# main.net
KiCad netlist of a schematic drawn in EAGLE
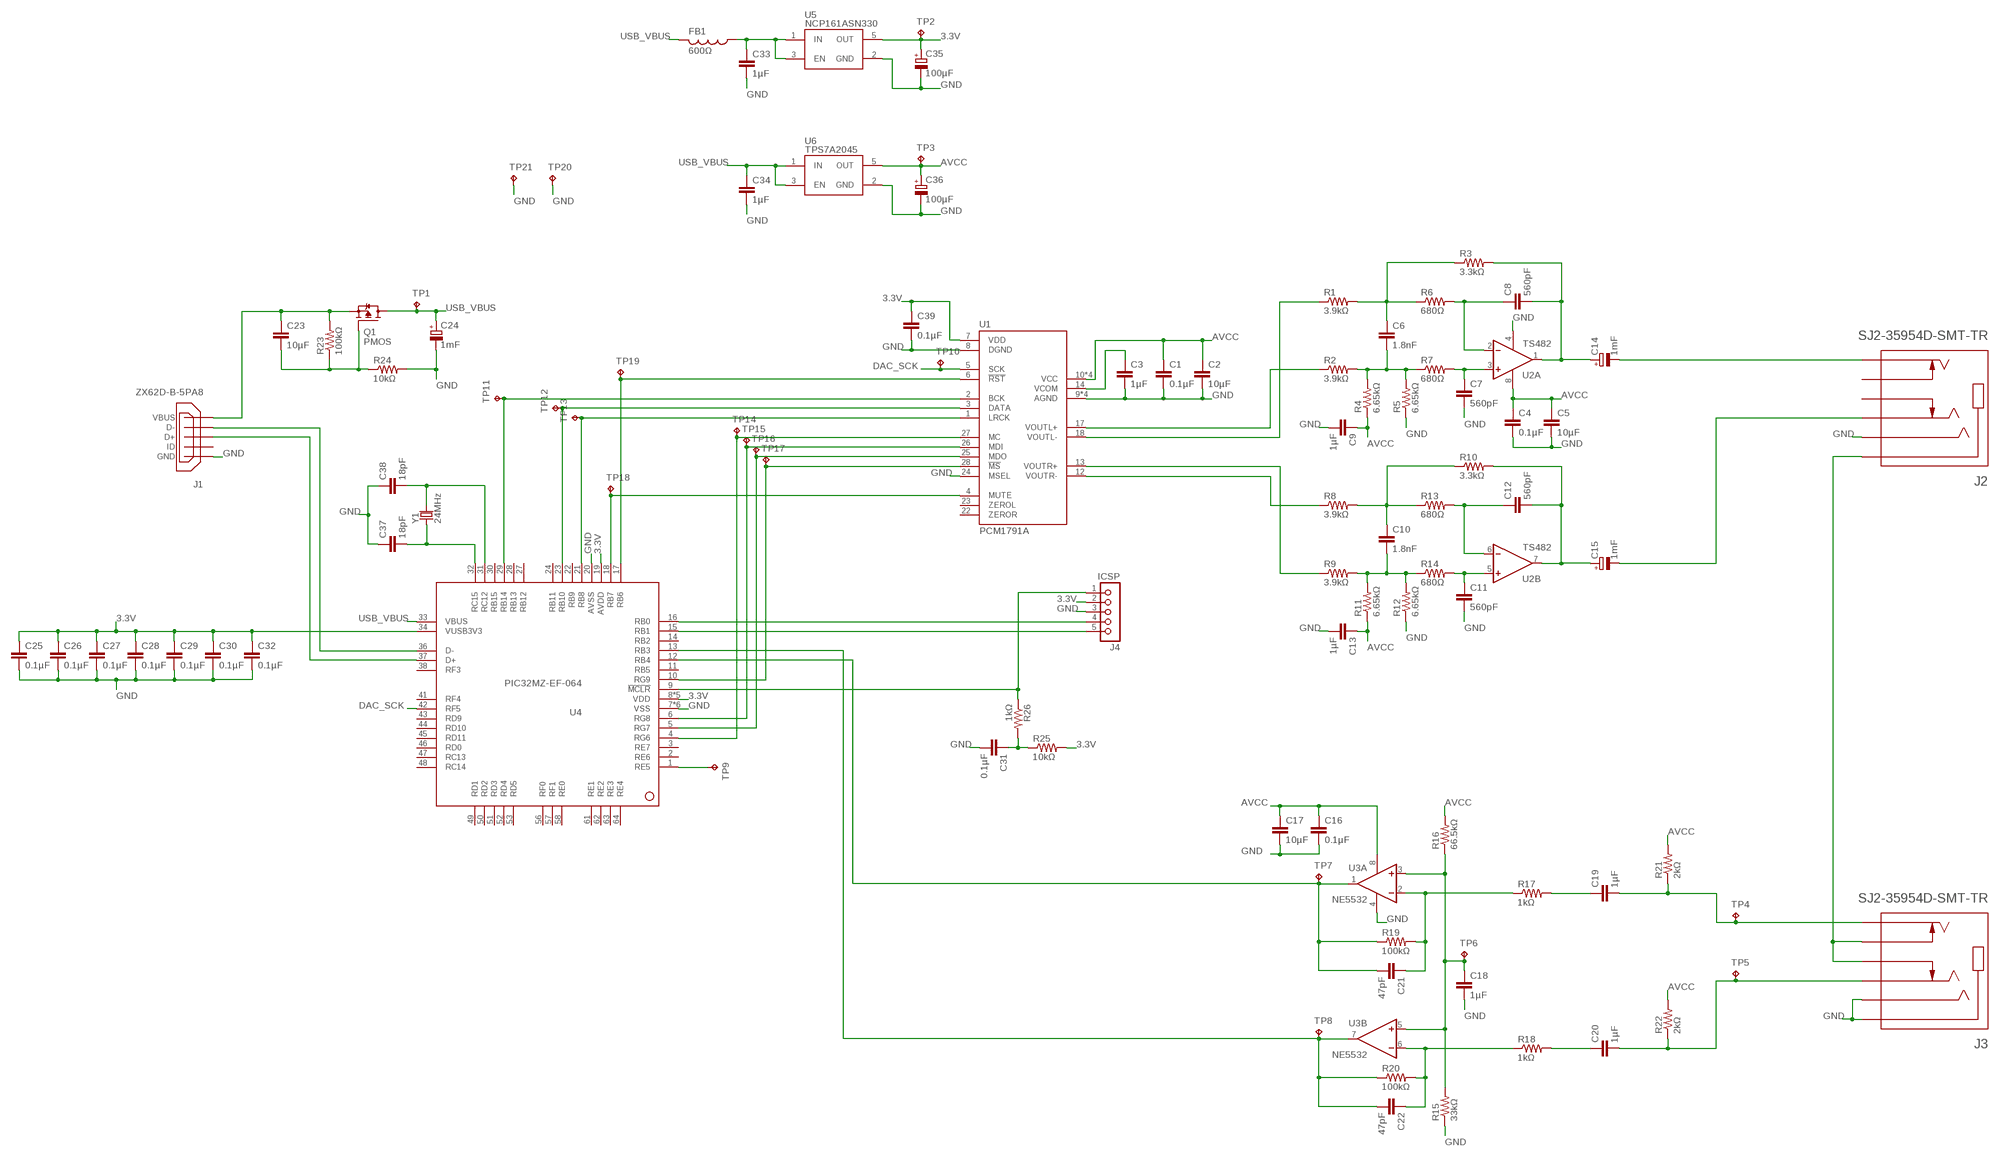
[diagram p0: schematic, sheet 1]

(export (version "E")
  (design (tool "Eeschema 10.0.6"))
  (components
    (comp (ref "C1")
      (value "0.1µF")
      (footprint "eagle-import:C0603")
      (libsource (lib "eagle-import") (part "C-EUC0603"))
    )
    (comp (ref "C2")
      (value "10µF")
      (footprint "eagle-import:C0805")
      (libsource (lib "eagle-import") (part "C-EUC0805"))
    )
    (comp (ref "C3")
      (value "1µF")
      (footprint "eagle-import:C0805")
      (libsource (lib "eagle-import") (part "C-EUC0805"))
    )
    (comp (ref "C4")
      (value "0.1µF")
      (footprint "eagle-import:C0603")
      (libsource (lib "eagle-import") (part "C-EUC0603"))
    )
    (comp (ref "C5")
      (value "10µF")
      (footprint "eagle-import:C0805")
      (libsource (lib "eagle-import") (part "C-EUC0805"))
    )
    (comp (ref "C6")
      (value "1.8nF")
      (footprint "eagle-import:C0603")
      (libsource (lib "eagle-import") (part "C-EUC0603"))
    )
    (comp (ref "C7")
      (value "560pF")
      (footprint "eagle-import:C0603")
      (libsource (lib "eagle-import") (part "C-EUC0603"))
    )
    (comp (ref "C8")
      (value "560pF")
      (footprint "eagle-import:C0603")
      (libsource (lib "eagle-import") (part "C-EUC0603"))
    )
    (comp (ref "C9")
      (value "1µF")
      (footprint "eagle-import:C0805")
      (libsource (lib "eagle-import") (part "C-EUC0805"))
    )
    (comp (ref "C10")
      (value "1.8nF")
      (footprint "eagle-import:C0603")
      (libsource (lib "eagle-import") (part "C-EUC0603"))
    )
    (comp (ref "C11")
      (value "560pF")
      (footprint "eagle-import:C0603")
      (libsource (lib "eagle-import") (part "C-EUC0603"))
    )
    (comp (ref "C12")
      (value "560pF")
      (footprint "eagle-import:C0603")
      (libsource (lib "eagle-import") (part "C-EUC0603"))
    )
    (comp (ref "C13")
      (value "1µF")
      (footprint "eagle-import:C0805")
      (libsource (lib "eagle-import") (part "C-EUC0805"))
    )
    (comp (ref "C14")
      (value "1mF")
      (footprint "eagle-import:E3,5-8-16-HORZ")
      (libsource (lib "eagle-import") (part "CAP-E3,5-8-16-HORZ"))
    )
    (comp (ref "C15")
      (value "1mF")
      (footprint "eagle-import:E3,5-8-16-HORZ")
      (libsource (lib "eagle-import") (part "CAP-E3,5-8-16-HORZ"))
    )
    (comp (ref "C16")
      (value "0.1µF")
      (footprint "eagle-import:C0603")
      (libsource (lib "eagle-import") (part "C-EUC0603"))
    )
    (comp (ref "C17")
      (value "10µF")
      (footprint "eagle-import:C0805")
      (libsource (lib "eagle-import") (part "C-EUC0805"))
    )
    (comp (ref "C18")
      (value "1µF")
      (footprint "eagle-import:C0805")
      (libsource (lib "eagle-import") (part "C-EUC0805"))
    )
    (comp (ref "C19")
      (value "1µF")
      (footprint "eagle-import:C050-050X075")
      (libsource (lib "eagle-import") (part "C-EU050-050X075"))
    )
    (comp (ref "C20")
      (value "1µF")
      (footprint "eagle-import:C050-050X075")
      (libsource (lib "eagle-import") (part "C-EU050-050X075"))
    )
    (comp (ref "C21")
      (value "47pF")
      (footprint "eagle-import:C050-045X075")
      (libsource (lib "eagle-import") (part "C-EU050-045X075"))
    )
    (comp (ref "C22")
      (value "47pF")
      (footprint "eagle-import:C050-045X075")
      (libsource (lib "eagle-import") (part "C-EU050-045X075"))
    )
    (comp (ref "C23")
      (value "10µF")
      (footprint "eagle-import:C0805")
      (libsource (lib "eagle-import") (part "C-EUC0805"))
    )
    (comp (ref "C24")
      (value "1mF")
      (footprint "eagle-import:E3,5-8-16-HORZ")
      (libsource (lib "eagle-import") (part "CAP-E3,5-8-16-HORZ"))
    )
    (comp (ref "C25")
      (value "0.1µF")
      (footprint "eagle-import:C0603")
      (libsource (lib "eagle-import") (part "C-EUC0603"))
    )
    (comp (ref "C26")
      (value "0.1µF")
      (footprint "eagle-import:C0603")
      (libsource (lib "eagle-import") (part "C-EUC0603"))
    )
    (comp (ref "C27")
      (value "0.1µF")
      (footprint "eagle-import:C0603")
      (libsource (lib "eagle-import") (part "C-EUC0603"))
    )
    (comp (ref "C28")
      (value "0.1µF")
      (footprint "eagle-import:C0603")
      (libsource (lib "eagle-import") (part "C-EUC0603"))
    )
    (comp (ref "C29")
      (value "0.1µF")
      (footprint "eagle-import:C0603")
      (libsource (lib "eagle-import") (part "C-EUC0603"))
    )
    (comp (ref "C30")
      (value "0.1µF")
      (footprint "eagle-import:C0603")
      (libsource (lib "eagle-import") (part "C-EUC0603"))
    )
    (comp (ref "C31")
      (value "0.1µF")
      (footprint "eagle-import:C0603")
      (libsource (lib "eagle-import") (part "C-EUC0603"))
    )
    (comp (ref "C32")
      (value "0.1µF")
      (footprint "eagle-import:C0603")
      (libsource (lib "eagle-import") (part "C-EUC0603"))
    )
    (comp (ref "C33")
      (value "1µF")
      (footprint "eagle-import:C0805")
      (libsource (lib "eagle-import") (part "C-EUC0805"))
    )
    (comp (ref "C34")
      (value "1µF")
      (footprint "eagle-import:C0805")
      (libsource (lib "eagle-import") (part "C-EUC0805"))
    )
    (comp (ref "C35")
      (value "100µF")
      (footprint "eagle-import:PANASONIC_D")
      (libsource (lib "eagle-import") (part "CPOL-EUD"))
    )
    (comp (ref "C36")
      (value "100µF")
      (footprint "eagle-import:PANASONIC_D")
      (libsource (lib "eagle-import") (part "CPOL-EUD"))
    )
    (comp (ref "C37")
      (value "18pF")
      (footprint "eagle-import:C0603")
      (libsource (lib "eagle-import") (part "C-EUC0603"))
    )
    (comp (ref "C38")
      (value "18pF")
      (footprint "eagle-import:C0603")
      (libsource (lib "eagle-import") (part "C-EUC0603"))
    )
    (comp (ref "C39")
      (value "0.1µF")
      (footprint "eagle-import:C0603")
      (libsource (lib "eagle-import") (part "C-EUC0603"))
    )
    (comp (ref "FB1")
      (value "600Ω")
      (footprint "eagle-import:C0603")
      (libsource (lib "eagle-import") (part "0603-FERRITE"))
    )
    (comp (ref "J1")
      (value "ZX62D-B-5PA8")
      (footprint "eagle-import:ZX62D-B-5PA8")
      (libsource (lib "eagle-import") (part "ZX62D-B-5PA8"))
    )
    (comp (ref "J2")
      (value "SJ2-35954D-SMT-TR")
      (footprint "eagle-import:CUI_SJ2-35954D-SMT-TR")
      (fields (field (name "MANUFACTURER") "CUI"))
      (libsource (lib "eagle-import") (part "SJ2-35954D-SMT-TR"))
    )
    (comp (ref "J3")
      (value "SJ2-35954D-SMT-TR")
      (footprint "eagle-import:CUI_SJ2-35954D-SMT-TR")
      (fields (field (name "MANUFACTURER") "CUI"))
      (libsource (lib "eagle-import") (part "SJ2-35954D-SMT-TR"))
    )
    (comp (ref "J4")
      (value "ICSP")
      (footprint "eagle-import:5PIN-1.27")
      (libsource (lib "eagle-import") (part "5PIN-1.27"))
    )
    (comp (ref "Q1")
      (value "PMOS")
      (footprint "eagle-import:SOT23")
      (libsource (lib "eagle-import") (part "SOT23-P-MOSFET"))
    )
    (comp (ref "R1")
      (value "3.9kΩ")
      (footprint "eagle-import:R0603")
      (libsource (lib "eagle-import") (part "R-US_R0603"))
    )
    (comp (ref "R2")
      (value "3.9kΩ")
      (footprint "eagle-import:R0603")
      (libsource (lib "eagle-import") (part "R-US_R0603"))
    )
    (comp (ref "R3")
      (value "3.3kΩ")
      (footprint "eagle-import:R0603")
      (libsource (lib "eagle-import") (part "R-US_R0603"))
    )
    (comp (ref "R4")
      (value "6.65kΩ")
      (footprint "eagle-import:R0603")
      (libsource (lib "eagle-import") (part "R-US_R0603"))
    )
    (comp (ref "R5")
      (value "6.65kΩ")
      (footprint "eagle-import:R0603")
      (libsource (lib "eagle-import") (part "R-US_R0603"))
    )
    (comp (ref "R6")
      (value "680Ω")
      (footprint "eagle-import:R0603")
      (libsource (lib "eagle-import") (part "R-US_R0603"))
    )
    (comp (ref "R7")
      (value "680Ω")
      (footprint "eagle-import:R0603")
      (libsource (lib "eagle-import") (part "R-US_R0603"))
    )
    (comp (ref "R8")
      (value "3.9kΩ")
      (footprint "eagle-import:R0603")
      (libsource (lib "eagle-import") (part "R-US_R0603"))
    )
    (comp (ref "R9")
      (value "3.9kΩ")
      (footprint "eagle-import:R0603")
      (libsource (lib "eagle-import") (part "R-US_R0603"))
    )
    (comp (ref "R10")
      (value "3.3kΩ")
      (footprint "eagle-import:R0603")
      (libsource (lib "eagle-import") (part "R-US_R0603"))
    )
    (comp (ref "R11")
      (value "6.65kΩ")
      (footprint "eagle-import:R0603")
      (libsource (lib "eagle-import") (part "R-US_R0603"))
    )
    (comp (ref "R12")
      (value "6.65kΩ")
      (footprint "eagle-import:R0603")
      (libsource (lib "eagle-import") (part "R-US_R0603"))
    )
    (comp (ref "R13")
      (value "680Ω")
      (footprint "eagle-import:R0603")
      (libsource (lib "eagle-import") (part "R-US_R0603"))
    )
    (comp (ref "R14")
      (value "680Ω")
      (footprint "eagle-import:R0603")
      (libsource (lib "eagle-import") (part "R-US_R0603"))
    )
    (comp (ref "R15")
      (value "33kΩ")
      (footprint "eagle-import:R0603")
      (libsource (lib "eagle-import") (part "R-US_R0603"))
    )
    (comp (ref "R16")
      (value "66.5kΩ")
      (footprint "eagle-import:R0603")
      (libsource (lib "eagle-import") (part "R-US_R0603"))
    )
    (comp (ref "R17")
      (value "1kΩ")
      (footprint "eagle-import:R0603")
      (libsource (lib "eagle-import") (part "R-US_R0603"))
    )
    (comp (ref "R18")
      (value "1kΩ")
      (footprint "eagle-import:R0603")
      (libsource (lib "eagle-import") (part "R-US_R0603"))
    )
    (comp (ref "R19")
      (value "100kΩ")
      (footprint "eagle-import:R0603")
      (libsource (lib "eagle-import") (part "R-US_R0603"))
    )
    (comp (ref "R20")
      (value "100kΩ")
      (footprint "eagle-import:R0603")
      (libsource (lib "eagle-import") (part "R-US_R0603"))
    )
    (comp (ref "R21")
      (value "2kΩ")
      (footprint "eagle-import:R0603")
      (libsource (lib "eagle-import") (part "R-US_R0603"))
    )
    (comp (ref "R22")
      (value "2kΩ")
      (footprint "eagle-import:R0603")
      (libsource (lib "eagle-import") (part "R-US_R0603"))
    )
    (comp (ref "R23")
      (value "100kΩ")
      (footprint "eagle-import:R0603")
      (libsource (lib "eagle-import") (part "R-US_R0603"))
    )
    (comp (ref "R24")
      (value "10kΩ")
      (footprint "eagle-import:R0603")
      (libsource (lib "eagle-import") (part "R-US_R0603"))
    )
    (comp (ref "R25")
      (value "10kΩ")
      (footprint "eagle-import:R0603")
      (libsource (lib "eagle-import") (part "R-US_R0603"))
    )
    (comp (ref "R26")
      (value "1kΩ")
      (footprint "eagle-import:R0603")
      (libsource (lib "eagle-import") (part "R-US_R0603"))
    )
    (comp (ref "TP1")
      (value "RCU-0(J)")
      (footprint "eagle-import:TP_0603_JOINED")
      (libsource (lib "eagle-import") (part "RCU-0(J)"))
    )
    (comp (ref "TP2")
      (value "RCU-0(J)")
      (footprint "eagle-import:TP_0603_JOINED")
      (libsource (lib "eagle-import") (part "RCU-0(J)"))
    )
    (comp (ref "TP3")
      (value "RCU-0(J)")
      (footprint "eagle-import:TP_0603_JOINED")
      (libsource (lib "eagle-import") (part "RCU-0(J)"))
    )
    (comp (ref "TP4")
      (value "RCU-0(J)")
      (footprint "eagle-import:TP_0603_JOINED")
      (libsource (lib "eagle-import") (part "RCU-0(J)"))
    )
    (comp (ref "TP5")
      (value "RCU-0(J)")
      (footprint "eagle-import:TP_0603_JOINED")
      (libsource (lib "eagle-import") (part "RCU-0(J)"))
    )
    (comp (ref "TP6")
      (value "RCU-0(J)")
      (footprint "eagle-import:TP_0603_JOINED")
      (libsource (lib "eagle-import") (part "RCU-0(J)"))
    )
    (comp (ref "TP7")
      (value "RCU-0(J)")
      (footprint "eagle-import:TP_0603_JOINED")
      (libsource (lib "eagle-import") (part "RCU-0(J)"))
    )
    (comp (ref "TP8")
      (value "RCU-0(J)")
      (footprint "eagle-import:TP_0603_JOINED")
      (libsource (lib "eagle-import") (part "RCU-0(J)"))
    )
    (comp (ref "TP9")
      (value "RCU-0(J)")
      (footprint "eagle-import:TP_0603_JOINED")
      (libsource (lib "eagle-import") (part "RCU-0(J)"))
    )
    (comp (ref "TP10")
      (value "RCU-0(J)")
      (footprint "eagle-import:TP_0603_JOINED")
      (libsource (lib "eagle-import") (part "RCU-0(J)"))
    )
    (comp (ref "TP11")
      (value "RCU-0(J)")
      (footprint "eagle-import:TP_0603_JOINED")
      (libsource (lib "eagle-import") (part "RCU-0(J)"))
    )
    (comp (ref "TP12")
      (value "RCU-0(J)")
      (footprint "eagle-import:TP_0603_JOINED")
      (libsource (lib "eagle-import") (part "RCU-0(J)"))
    )
    (comp (ref "TP13")
      (value "RCU-0(J)")
      (footprint "eagle-import:TP_0603_JOINED")
      (libsource (lib "eagle-import") (part "RCU-0(J)"))
    )
    (comp (ref "TP14")
      (value "RCU-0(J)")
      (footprint "eagle-import:TP_0603_JOINED")
      (libsource (lib "eagle-import") (part "RCU-0(J)"))
    )
    (comp (ref "TP15")
      (value "RCU-0(J)")
      (footprint "eagle-import:TP_0603_JOINED")
      (libsource (lib "eagle-import") (part "RCU-0(J)"))
    )
    (comp (ref "TP16")
      (value "RCU-0(J)")
      (footprint "eagle-import:TP_0603_JOINED")
      (libsource (lib "eagle-import") (part "RCU-0(J)"))
    )
    (comp (ref "TP17")
      (value "RCU-0(J)")
      (footprint "eagle-import:TP_0603_JOINED")
      (libsource (lib "eagle-import") (part "RCU-0(J)"))
    )
    (comp (ref "TP18")
      (value "RCU-0(J)")
      (footprint "eagle-import:TP_0603_JOINED")
      (libsource (lib "eagle-import") (part "RCU-0(J)"))
    )
    (comp (ref "TP19")
      (value "RCU-0(J)")
      (footprint "eagle-import:TP_0603_JOINED")
      (libsource (lib "eagle-import") (part "RCU-0(J)"))
    )
    (comp (ref "TP20")
      (value "RCU-0(J)")
      (footprint "eagle-import:TP_0603_JOINED")
      (libsource (lib "eagle-import") (part "RCU-0(J)"))
    )
    (comp (ref "TP21")
      (value "RCU-0(J)")
      (footprint "eagle-import:TP_0603_JOINED")
      (libsource (lib "eagle-import") (part "RCU-0(J)"))
    )
    (comp (ref "U1")
      (value "PCM1791A")
      (footprint "eagle-import:SSOP28")
      (libsource (lib "eagle-import") (part "PCM1791A"))
    )
    (comp (ref "U2")
      (value "TS482")
      (footprint "eagle-import:MSOP8")
      (libsource (lib "eagle-import") (part "TS482"))
    )
    (comp (ref "U3")
      (value "NE5532")
      (footprint "eagle-import:SOIC8")
      (libsource (lib "eagle-import") (part "NE5532"))
    )
    (comp (ref "U4")
      (value "PIC32MZ-EF-064")
      (footprint "eagle-import:TQFP64-10X10X1MM")
      (libsource (lib "eagle-import") (part "PIC32MZ-EF-064"))
    )
    (comp (ref "U5")
      (value "NCP161ASN330")
      (footprint "eagle-import:SOT23-5L")
      (libsource (lib "eagle-import") (part "SOT23-5-LDO"))
    )
    (comp (ref "U6")
      (value "TPS7A2045")
      (footprint "eagle-import:SOT23-5L")
      (libsource (lib "eagle-import") (part "SOT23-5-LDO"))
    )
    (comp (ref "Y1")
      (value "24MHz")
      (footprint "eagle-import:HC49_4HSMX")
      (libsource (lib "eagle-import") (part "HC49/4HSMX-CRYSTAL"))
    )
  )
  (nets
    (net (code "1") (name "/3.3V") (class "Default")
      (node (ref "C25") (pin "1") (pinfunction "1_1") (pintype "passive"))
      (node (ref "C26") (pin "1") (pinfunction "1_1") (pintype "passive"))
      (node (ref "C27") (pin "1") (pinfunction "1_1") (pintype "passive"))
      (node (ref "C28") (pin "1") (pinfunction "1_1") (pintype "passive"))
      (node (ref "C29") (pin "1") (pinfunction "1_1") (pintype "passive"))
      (node (ref "C30") (pin "1") (pinfunction "1_1") (pintype "passive"))
      (node (ref "C32") (pin "1") (pinfunction "1_1") (pintype "passive"))
      (node (ref "C35") (pin "+") (pinfunction "+_+") (pintype "passive"))
      (node (ref "C39") (pin "1") (pinfunction "1_1") (pintype "passive"))
      (node (ref "J4") (pin "2") (pinfunction "2_2") (pintype "passive"))
      (node (ref "R25") (pin "2") (pinfunction "2_2") (pintype "passive"))
      (node (ref "TP2") (pin "1") (pinfunction "TP_1") (pintype "input"))
      (node (ref "U1") (pin "7") (pinfunction "VDD_7") (pintype "bidirectional"))
      (node (ref "U4") (pin "19") (pinfunction "AVDD_19") (pintype "bidirectional"))
      (node (ref "U4") (pin "26") (pinfunction "VDD_26") (pintype "bidirectional"))
      (node (ref "U4") (pin "34") (pinfunction "VUSB3V3_34") (pintype "bidirectional"))
      (node (ref "U4") (pin "39") (pinfunction "VDD_39") (pintype "bidirectional"))
      (node (ref "U4") (pin "54") (pinfunction "VDD_54") (pintype "bidirectional"))
      (node (ref "U4") (pin "60") (pinfunction "VDD_60") (pintype "bidirectional"))
      (node (ref "U4") (pin "8") (pinfunction "VDD_8") (pintype "bidirectional"))
      (node (ref "U5") (pin "5") (pinfunction "OUT_5") (pintype "bidirectional"))
    )
    (net (code "2") (name "/AVCC") (class "Default")
      (node (ref "C1") (pin "1") (pinfunction "1_1") (pintype "passive"))
      (node (ref "C13") (pin "1") (pinfunction "1_1") (pintype "passive"))
      (node (ref "C16") (pin "1") (pinfunction "1_1") (pintype "passive"))
      (node (ref "C17") (pin "1") (pinfunction "1_1") (pintype "passive"))
      (node (ref "C2") (pin "1") (pinfunction "1_1") (pintype "passive"))
      (node (ref "C36") (pin "+") (pinfunction "+_+") (pintype "passive"))
      (node (ref "C4") (pin "1") (pinfunction "1_1") (pintype "passive"))
      (node (ref "C5") (pin "1") (pinfunction "1_1") (pintype "passive"))
      (node (ref "C9") (pin "1") (pinfunction "1_1") (pintype "passive"))
      (node (ref "R11") (pin "1") (pinfunction "1_1") (pintype "passive"))
      (node (ref "R16") (pin "2") (pinfunction "2_2") (pintype "passive"))
      (node (ref "R21") (pin "2") (pinfunction "2_2") (pintype "passive"))
      (node (ref "R22") (pin "2") (pinfunction "2_2") (pintype "passive"))
      (node (ref "R4") (pin "1") (pinfunction "1_1") (pintype "passive"))
      (node (ref "TP3") (pin "1") (pinfunction "TP_1") (pintype "input"))
      (node (ref "U1") (pin "10") (pinfunction "VCC_10") (pintype "bidirectional"))
      (node (ref "U1") (pin "15") (pinfunction "VCC_15") (pintype "bidirectional"))
      (node (ref "U1") (pin "20") (pinfunction "VCC_20") (pintype "bidirectional"))
      (node (ref "U1") (pin "21") (pinfunction "VCC_21") (pintype "bidirectional"))
      (node (ref "U2") (pin "8") (pinfunction "V+_8") (pintype "power_in"))
      (node (ref "U3") (pin "8") (pinfunction "V+_8") (pintype "power_in"))
      (node (ref "U6") (pin "5") (pinfunction "OUT_5") (pintype "bidirectional"))
    )
    (net (code "3") (name "/DAC_SCK") (class "Default")
      (node (ref "TP10") (pin "1") (pinfunction "TP_1") (pintype "input"))
      (node (ref "U1") (pin "5") (pinfunction "SCK_5") (pintype "bidirectional"))
      (node (ref "U4") (pin "42") (pinfunction "RF5_42") (pintype "bidirectional"))
    )
    (net (code "4") (name "/GND") (class "Default")
      (node (ref "C1") (pin "2") (pinfunction "2_2") (pintype "passive"))
      (node (ref "C11") (pin "2") (pinfunction "2_2") (pintype "passive"))
      (node (ref "C13") (pin "2") (pinfunction "2_2") (pintype "passive"))
      (node (ref "C16") (pin "2") (pinfunction "2_2") (pintype "passive"))
      (node (ref "C17") (pin "2") (pinfunction "2_2") (pintype "passive"))
      (node (ref "C18") (pin "2") (pinfunction "2_2") (pintype "passive"))
      (node (ref "C2") (pin "2") (pinfunction "2_2") (pintype "passive"))
      (node (ref "C24") (pin "-") (pinfunction "-_-") (pintype "passive"))
      (node (ref "C25") (pin "2") (pinfunction "2_2") (pintype "passive"))
      (node (ref "C26") (pin "2") (pinfunction "2_2") (pintype "passive"))
      (node (ref "C27") (pin "2") (pinfunction "2_2") (pintype "passive"))
      (node (ref "C28") (pin "2") (pinfunction "2_2") (pintype "passive"))
      (node (ref "C29") (pin "2") (pinfunction "2_2") (pintype "passive"))
      (node (ref "C3") (pin "2") (pinfunction "2_2") (pintype "passive"))
      (node (ref "C30") (pin "2") (pinfunction "2_2") (pintype "passive"))
      (node (ref "C31") (pin "2") (pinfunction "2_2") (pintype "passive"))
      (node (ref "C32") (pin "2") (pinfunction "2_2") (pintype "passive"))
      (node (ref "C33") (pin "2") (pinfunction "2_2") (pintype "passive"))
      (node (ref "C34") (pin "2") (pinfunction "2_2") (pintype "passive"))
      (node (ref "C35") (pin "-") (pinfunction "-_-") (pintype "passive"))
      (node (ref "C36") (pin "-") (pinfunction "-_-") (pintype "passive"))
      (node (ref "C37") (pin "1") (pinfunction "1_1") (pintype "passive"))
      (node (ref "C38") (pin "1") (pinfunction "1_1") (pintype "passive"))
      (node (ref "C39") (pin "2") (pinfunction "2_2") (pintype "passive"))
      (node (ref "C4") (pin "2") (pinfunction "2_2") (pintype "passive"))
      (node (ref "C5") (pin "2") (pinfunction "2_2") (pintype "passive"))
      (node (ref "C7") (pin "2") (pinfunction "2_2") (pintype "passive"))
      (node (ref "C9") (pin "2") (pinfunction "2_2") (pintype "passive"))
      (node (ref "J1") (pin "5") (pinfunction "GND_5") (pintype "passive"))
      (node (ref "J1") (pin "S1") (pinfunction "GND_S1") (pintype "passive"))
      (node (ref "J1") (pin "S2") (pinfunction "GND_S2") (pintype "passive"))
      (node (ref "J1") (pin "S3") (pinfunction "GND_S3") (pintype "passive"))
      (node (ref "J1") (pin "S4") (pinfunction "GND_S4") (pintype "passive"))
      (node (ref "J2") (pin "4") (pinfunction "RING2_4") (pintype "passive"))
      (node (ref "J3") (pin "1") (pinfunction "SLEEVE_1") (pintype "passive"))
      (node (ref "J3") (pin "4") (pinfunction "RING2_4") (pintype "passive"))
      (node (ref "J4") (pin "3") (pinfunction "3_3") (pintype "passive"))
      (node (ref "R12") (pin "1") (pinfunction "1_1") (pintype "passive"))
      (node (ref "R15") (pin "1") (pinfunction "1_1") (pintype "passive"))
      (node (ref "R24") (pin "2") (pinfunction "2_2") (pintype "passive"))
      (node (ref "R5") (pin "1") (pinfunction "1_1") (pintype "passive"))
      (node (ref "TP20") (pin "1") (pinfunction "TP_1") (pintype "input"))
      (node (ref "TP21") (pin "1") (pinfunction "TP_1") (pintype "input"))
      (node (ref "U1") (pin "11") (pinfunction "AGND_11") (pintype "bidirectional"))
      (node (ref "U1") (pin "16") (pinfunction "AGND_16") (pintype "bidirectional"))
      (node (ref "U1") (pin "19") (pinfunction "AGND_19") (pintype "bidirectional"))
      (node (ref "U1") (pin "24") (pinfunction "MSEL_24") (pintype "bidirectional"))
      (node (ref "U1") (pin "8") (pinfunction "DGND_8") (pintype "bidirectional"))
      (node (ref "U1") (pin "9") (pinfunction "AGND_9") (pintype "bidirectional"))
      (node (ref "U2") (pin "4") (pinfunction "V-_4") (pintype "power_in"))
      (node (ref "U3") (pin "4") (pinfunction "V-_4") (pintype "power_in"))
      (node (ref "U4") (pin "20") (pinfunction "AVSS_20") (pintype "bidirectional"))
      (node (ref "U4") (pin "25") (pinfunction "VSS_25") (pintype "bidirectional"))
      (node (ref "U4") (pin "35") (pinfunction "VSS_35") (pintype "bidirectional"))
      (node (ref "U4") (pin "40") (pinfunction "VSS_40") (pintype "bidirectional"))
      (node (ref "U4") (pin "55") (pinfunction "VSS_55") (pintype "bidirectional"))
      (node (ref "U4") (pin "59") (pinfunction "VSS_59") (pintype "bidirectional"))
      (node (ref "U4") (pin "7") (pinfunction "VSS_7") (pintype "bidirectional"))
      (node (ref "U5") (pin "2") (pinfunction "GND_2") (pintype "bidirectional"))
      (node (ref "U6") (pin "2") (pinfunction "GND_2") (pintype "bidirectional"))
    )
    (net (code "5") (name "/USB_VBUS") (class "Default")
      (node (ref "C24") (pin "+") (pinfunction "+_+") (pintype "passive"))
      (node (ref "C34") (pin "1") (pinfunction "1_1") (pintype "passive"))
      (node (ref "FB1") (pin "2") (pinfunction "2_2") (pintype "passive"))
      (node (ref "Q1") (pin "3") (pinfunction "D_3") (pintype "passive"))
      (node (ref "TP1") (pin "1") (pinfunction "TP_1") (pintype "input"))
      (node (ref "U4") (pin "33") (pinfunction "VBUS_33") (pintype "bidirectional"))
      (node (ref "U6") (pin "1") (pinfunction "IN_1") (pintype "bidirectional"))
      (node (ref "U6") (pin "3") (pinfunction "EN_3") (pintype "bidirectional"))
    )
    (net (code "6") (name "Net-(C6-Pad1)") (class "Default")
      (node (ref "C6") (pin "1") (pinfunction "1_1") (pintype "passive"))
      (node (ref "R1") (pin "2") (pinfunction "2_2") (pintype "passive"))
      (node (ref "R3") (pin "1") (pinfunction "1_1") (pintype "passive"))
      (node (ref "R6") (pin "1") (pinfunction "1_1") (pintype "passive"))
    )
    (net (code "7") (name "Net-(C6-Pad2)") (class "Default")
      (node (ref "C6") (pin "2") (pinfunction "2_2") (pintype "passive"))
      (node (ref "R2") (pin "2") (pinfunction "2_2") (pintype "passive"))
      (node (ref "R4") (pin "2") (pinfunction "2_2") (pintype "passive"))
      (node (ref "R5") (pin "2") (pinfunction "2_2") (pintype "passive"))
      (node (ref "R7") (pin "1") (pinfunction "1_1") (pintype "passive"))
    )
    (net (code "8") (name "Net-(C10-Pad1)") (class "Default")
      (node (ref "C10") (pin "1") (pinfunction "1_1") (pintype "passive"))
      (node (ref "R10") (pin "1") (pinfunction "1_1") (pintype "passive"))
      (node (ref "R13") (pin "1") (pinfunction "1_1") (pintype "passive"))
      (node (ref "R8") (pin "2") (pinfunction "2_2") (pintype "passive"))
    )
    (net (code "9") (name "Net-(C10-Pad2)") (class "Default")
      (node (ref "C10") (pin "2") (pinfunction "2_2") (pintype "passive"))
      (node (ref "R11") (pin "2") (pinfunction "2_2") (pintype "passive"))
      (node (ref "R12") (pin "2") (pinfunction "2_2") (pintype "passive"))
      (node (ref "R14") (pin "1") (pinfunction "1_1") (pintype "passive"))
      (node (ref "R9") (pin "2") (pinfunction "2_2") (pintype "passive"))
    )
    (net (code "10") (name "Net-(C19-Pad1)") (class "Default")
      (node (ref "C19") (pin "1") (pinfunction "1_1") (pintype "passive"))
      (node (ref "R17") (pin "2") (pinfunction "2_2") (pintype "passive"))
    )
    (net (code "11") (name "Net-(C20-Pad1)") (class "Default")
      (node (ref "C20") (pin "1") (pinfunction "1_1") (pintype "passive"))
      (node (ref "R18") (pin "2") (pinfunction "2_2") (pintype "passive"))
    )
    (net (code "12") (name "Net-(C31-Pad1)") (class "Default")
      (node (ref "C31") (pin "1") (pinfunction "1_1") (pintype "passive"))
      (node (ref "R25") (pin "1") (pinfunction "1_1") (pintype "passive"))
      (node (ref "R26") (pin "2") (pinfunction "2_2") (pintype "passive"))
    )
    (net (code "13") (name "Net-(J1-D+)") (class "Default")
      (node (ref "J1") (pin "3") (pinfunction "D+_3") (pintype "passive"))
      (node (ref "U4") (pin "37") (pinfunction "D+_37") (pintype "bidirectional"))
    )
    (net (code "14") (name "Net-(J1-D-)") (class "Default")
      (node (ref "J1") (pin "2") (pinfunction "D-_2") (pintype "passive"))
      (node (ref "U4") (pin "36") (pinfunction "D-_36") (pintype "bidirectional"))
    )
    (net (code "15") (name "Net-(J1-VBUS)") (class "Default")
      (node (ref "C23") (pin "1") (pinfunction "1_1") (pintype "passive"))
      (node (ref "J1") (pin "1") (pinfunction "VBUS_1") (pintype "passive"))
      (node (ref "Q1") (pin "2") (pinfunction "S_2") (pintype "passive"))
      (node (ref "R23") (pin "2") (pinfunction "2_2") (pintype "passive"))
    )
    (net (code "16") (name "Net-(J2-RING1)") (class "Default")
      (node (ref "C15") (pin "-") (pinfunction "-_-") (pintype "passive"))
      (node (ref "J2") (pin "3") (pinfunction "RING1_3") (pintype "passive"))
    )
    (net (code "17") (name "Net-(J2-SLEEVE)") (class "Default")
      (node (ref "J2") (pin "1") (pinfunction "SLEEVE_1") (pintype "passive"))
      (node (ref "J3") (pin "10") (pinfunction "TIP_SWITCH_10") (pintype "passive"))
      (node (ref "J3") (pin "11") (pinfunction "RING1_SWITCH_11") (pintype "passive"))
    )
    (net (code "18") (name "Net-(J2-TIP)") (class "Default")
      (node (ref "C14") (pin "-") (pinfunction "-_-") (pintype "passive"))
      (node (ref "J2") (pin "2") (pinfunction "TIP_2") (pintype "passive"))
    )
    (net (code "19") (name "Net-(J3-RING1)") (class "Default")
      (node (ref "C20") (pin "2") (pinfunction "2_2") (pintype "passive"))
      (node (ref "J3") (pin "3") (pinfunction "RING1_3") (pintype "passive"))
      (node (ref "R22") (pin "1") (pinfunction "1_1") (pintype "passive"))
      (node (ref "TP5") (pin "1") (pinfunction "TP_1") (pintype "input"))
    )
    (net (code "20") (name "Net-(J3-TIP)") (class "Default")
      (node (ref "C19") (pin "2") (pinfunction "2_2") (pintype "passive"))
      (node (ref "J3") (pin "2") (pinfunction "TIP_2") (pintype "passive"))
      (node (ref "R21") (pin "1") (pinfunction "1_1") (pintype "passive"))
      (node (ref "TP4") (pin "1") (pinfunction "TP_1") (pintype "input"))
    )
    (net (code "21") (name "Net-(Q1-G)") (class "Default")
      (node (ref "C23") (pin "2") (pinfunction "2_2") (pintype "passive"))
      (node (ref "Q1") (pin "1") (pinfunction "G_1") (pintype "passive"))
      (node (ref "R23") (pin "1") (pinfunction "1_1") (pintype "passive"))
      (node (ref "R24") (pin "1") (pinfunction "1_1") (pintype "passive"))
    )
    (net (code "22") (name "Net-(TP6-TP)") (class "Default")
      (node (ref "C18") (pin "1") (pinfunction "1_1") (pintype "passive"))
      (node (ref "R15") (pin "2") (pinfunction "2_2") (pintype "passive"))
      (node (ref "R16") (pin "1") (pinfunction "1_1") (pintype "passive"))
      (node (ref "TP6") (pin "1") (pinfunction "TP_1") (pintype "input"))
      (node (ref "U3") (pin "3") (pinfunction "+IN_3") (pintype "input"))
      (node (ref "U3") (pin "5") (pinfunction "+IN_5") (pintype "input"))
    )
    (net (code "23") (name "Net-(TP7-TP)") (class "Default")
      (node (ref "C21") (pin "2") (pinfunction "2_2") (pintype "passive"))
      (node (ref "R19") (pin "1") (pinfunction "1_1") (pintype "passive"))
      (node (ref "TP7") (pin "1") (pinfunction "TP_1") (pintype "input"))
      (node (ref "U3") (pin "1") (pinfunction "OUT_1") (pintype "output"))
      (node (ref "U4") (pin "12") (pinfunction "RB4_12") (pintype "bidirectional"))
    )
    (net (code "24") (name "Net-(TP8-TP)") (class "Default")
      (node (ref "C22") (pin "2") (pinfunction "2_2") (pintype "passive"))
      (node (ref "R20") (pin "1") (pinfunction "1_1") (pintype "passive"))
      (node (ref "TP8") (pin "1") (pinfunction "TP_1") (pintype "input"))
      (node (ref "U3") (pin "7") (pinfunction "OUT_7") (pintype "output"))
      (node (ref "U4") (pin "13") (pinfunction "RB3_13") (pintype "bidirectional"))
    )
    (net (code "25") (name "Net-(TP9-TP)") (class "Default")
      (node (ref "TP9") (pin "1") (pinfunction "TP_1") (pintype "input"))
      (node (ref "U4") (pin "1") (pinfunction "RE5_1") (pintype "bidirectional"))
    )
    (net (code "26") (name "Net-(TP11-TP)") (class "Default")
      (node (ref "TP11") (pin "1") (pinfunction "TP_1") (pintype "input"))
      (node (ref "U1") (pin "2") (pinfunction "BCK_2") (pintype "bidirectional"))
      (node (ref "U4") (pin "29") (pinfunction "RB14_29") (pintype "bidirectional"))
    )
    (net (code "27") (name "Net-(TP12-TP)") (class "Default")
      (node (ref "TP12") (pin "1") (pinfunction "TP_1") (pintype "input"))
      (node (ref "U1") (pin "3") (pinfunction "DATA_3") (pintype "bidirectional"))
      (node (ref "U4") (pin "23") (pinfunction "RB10_23") (pintype "bidirectional"))
    )
    (net (code "28") (name "Net-(TP13-TP)") (class "Default")
      (node (ref "TP13") (pin "1") (pinfunction "TP_1") (pintype "input"))
      (node (ref "U1") (pin "1") (pinfunction "LRCK_1") (pintype "bidirectional"))
      (node (ref "U4") (pin "21") (pinfunction "RB8_21") (pintype "bidirectional"))
    )
    (net (code "29") (name "Net-(TP14-TP)") (class "Default")
      (node (ref "TP14") (pin "1") (pinfunction "TP_1") (pintype "input"))
      (node (ref "U1") (pin "27") (pinfunction "MC_27") (pintype "bidirectional"))
      (node (ref "U4") (pin "4") (pinfunction "RG6_4") (pintype "bidirectional"))
    )
    (net (code "30") (name "Net-(TP15-TP)") (class "Default")
      (node (ref "TP15") (pin "1") (pinfunction "TP_1") (pintype "input"))
      (node (ref "U1") (pin "26") (pinfunction "MDI_26") (pintype "bidirectional"))
      (node (ref "U4") (pin "6") (pinfunction "RG8_6") (pintype "bidirectional"))
    )
    (net (code "31") (name "Net-(TP16-TP)") (class "Default")
      (node (ref "TP16") (pin "1") (pinfunction "TP_1") (pintype "input"))
      (node (ref "U1") (pin "25") (pinfunction "MDO_25") (pintype "bidirectional"))
      (node (ref "U4") (pin "5") (pinfunction "RG7_5") (pintype "bidirectional"))
    )
    (net (code "32") (name "Net-(TP17-TP)") (class "Default")
      (node (ref "TP17") (pin "1") (pinfunction "TP_1") (pintype "input"))
      (node (ref "U1") (pin "28") (pinfunction "~{MS}_28") (pintype "bidirectional"))
      (node (ref "U4") (pin "10") (pinfunction "RG9_10") (pintype "bidirectional"))
    )
    (net (code "33") (name "Net-(TP18-TP)") (class "Default")
      (node (ref "TP18") (pin "1") (pinfunction "TP_1") (pintype "input"))
      (node (ref "U1") (pin "4") (pinfunction "MUTE_4") (pintype "bidirectional"))
      (node (ref "U4") (pin "18") (pinfunction "RB7_18") (pintype "bidirectional"))
    )
    (net (code "34") (name "Net-(TP19-TP)") (class "Default")
      (node (ref "TP19") (pin "1") (pinfunction "TP_1") (pintype "input"))
      (node (ref "U1") (pin "6") (pinfunction "~{RST}_6") (pintype "bidirectional"))
      (node (ref "U4") (pin "17") (pinfunction "RB6_17") (pintype "bidirectional"))
    )
    (net (code "35") (name "Net-(U1-VCOM)") (class "Default")
      (node (ref "C3") (pin "1") (pinfunction "1_1") (pintype "passive"))
      (node (ref "U1") (pin "14") (pinfunction "VCOM_14") (pintype "bidirectional"))
    )
    (net (code "36") (name "Net-(U1-VOUTL+)") (class "Default")
      (node (ref "R2") (pin "1") (pinfunction "1_1") (pintype "passive"))
      (node (ref "U1") (pin "17") (pinfunction "VOUTL+_17") (pintype "bidirectional"))
    )
    (net (code "37") (name "Net-(U1-VOUTL-)") (class "Default")
      (node (ref "R1") (pin "1") (pinfunction "1_1") (pintype "passive"))
      (node (ref "U1") (pin "18") (pinfunction "VOUTL-_18") (pintype "bidirectional"))
    )
    (net (code "38") (name "Net-(U1-VOUTR+)") (class "Default")
      (node (ref "R9") (pin "1") (pinfunction "1_1") (pintype "passive"))
      (node (ref "U1") (pin "13") (pinfunction "VOUTR+_13") (pintype "bidirectional"))
    )
    (net (code "39") (name "Net-(U1-VOUTR-)") (class "Default")
      (node (ref "R8") (pin "1") (pinfunction "1_1") (pintype "passive"))
      (node (ref "U1") (pin "12") (pinfunction "VOUTR-_12") (pintype "bidirectional"))
    )
    (net (code "40") (name "Net-(U2A-+IN)") (class "Default")
      (node (ref "C7") (pin "1") (pinfunction "1_1") (pintype "passive"))
      (node (ref "R7") (pin "2") (pinfunction "2_2") (pintype "passive"))
      (node (ref "U2") (pin "3") (pinfunction "+IN_3") (pintype "input"))
    )
    (net (code "41") (name "Net-(U2A--IN)") (class "Default")
      (node (ref "C8") (pin "1") (pinfunction "1_1") (pintype "passive"))
      (node (ref "R6") (pin "2") (pinfunction "2_2") (pintype "passive"))
      (node (ref "U2") (pin "2") (pinfunction "-IN_2") (pintype "input"))
    )
    (net (code "42") (name "Net-(U2A-OUT)") (class "Default")
      (node (ref "C14") (pin "+") (pinfunction "+_+") (pintype "passive"))
      (node (ref "C8") (pin "2") (pinfunction "2_2") (pintype "passive"))
      (node (ref "R3") (pin "2") (pinfunction "2_2") (pintype "passive"))
      (node (ref "U2") (pin "1") (pinfunction "OUT_1") (pintype "output"))
    )
    (net (code "43") (name "Net-(U2B-+IN)") (class "Default")
      (node (ref "C11") (pin "1") (pinfunction "1_1") (pintype "passive"))
      (node (ref "R14") (pin "2") (pinfunction "2_2") (pintype "passive"))
      (node (ref "U2") (pin "5") (pinfunction "+IN_5") (pintype "input"))
    )
    (net (code "44") (name "Net-(U2B--IN)") (class "Default")
      (node (ref "C12") (pin "1") (pinfunction "1_1") (pintype "passive"))
      (node (ref "R13") (pin "2") (pinfunction "2_2") (pintype "passive"))
      (node (ref "U2") (pin "6") (pinfunction "-IN_6") (pintype "input"))
    )
    (net (code "45") (name "Net-(U2B-OUT)") (class "Default")
      (node (ref "C12") (pin "2") (pinfunction "2_2") (pintype "passive"))
      (node (ref "C15") (pin "+") (pinfunction "+_+") (pintype "passive"))
      (node (ref "R10") (pin "2") (pinfunction "2_2") (pintype "passive"))
      (node (ref "U2") (pin "7") (pinfunction "OUT_7") (pintype "output"))
    )
    (net (code "46") (name "Net-(U3A--IN)") (class "Default")
      (node (ref "C21") (pin "1") (pinfunction "1_1") (pintype "passive"))
      (node (ref "R17") (pin "1") (pinfunction "1_1") (pintype "passive"))
      (node (ref "R19") (pin "2") (pinfunction "2_2") (pintype "passive"))
      (node (ref "U3") (pin "2") (pinfunction "-IN_2") (pintype "input"))
    )
    (net (code "47") (name "Net-(U3B--IN)") (class "Default")
      (node (ref "C22") (pin "1") (pinfunction "1_1") (pintype "passive"))
      (node (ref "R18") (pin "1") (pinfunction "1_1") (pintype "passive"))
      (node (ref "R20") (pin "2") (pinfunction "2_2") (pintype "passive"))
      (node (ref "U3") (pin "6") (pinfunction "-IN_6") (pintype "input"))
    )
    (net (code "48") (name "Net-(U4-RB0)") (class "Default")
      (node (ref "J4") (pin "4") (pinfunction "4_4") (pintype "passive"))
      (node (ref "U4") (pin "16") (pinfunction "RB0_16") (pintype "bidirectional"))
    )
    (net (code "49") (name "Net-(U4-RB1)") (class "Default")
      (node (ref "J4") (pin "5") (pinfunction "5_5") (pintype "passive"))
      (node (ref "U4") (pin "15") (pinfunction "RB1_15") (pintype "bidirectional"))
    )
    (net (code "50") (name "Net-(U4-RC12)") (class "Default")
      (node (ref "C38") (pin "2") (pinfunction "2_2") (pintype "passive"))
      (node (ref "U4") (pin "31") (pinfunction "RC12_31") (pintype "bidirectional"))
      (node (ref "Y1") (pin "2") (pinfunction "2_2") (pintype "passive"))
    )
    (net (code "51") (name "Net-(U4-RC15)") (class "Default")
      (node (ref "C37") (pin "2") (pinfunction "2_2") (pintype "passive"))
      (node (ref "U4") (pin "32") (pinfunction "RC15_32") (pintype "bidirectional"))
      (node (ref "Y1") (pin "1") (pinfunction "1_1") (pintype "passive"))
    )
    (net (code "52") (name "Net-(U4-~{MCLR})") (class "Default")
      (node (ref "J4") (pin "1") (pinfunction "1_1") (pintype "passive"))
      (node (ref "R26") (pin "1") (pinfunction "1_1") (pintype "passive"))
      (node (ref "U4") (pin "9") (pinfunction "~{MCLR}_9") (pintype "bidirectional"))
    )
    (net (code "53") (name "Net-(U5-EN)") (class "Default")
      (node (ref "C33") (pin "1") (pinfunction "1_1") (pintype "passive"))
      (node (ref "FB1") (pin "1") (pinfunction "1_1") (pintype "passive"))
      (node (ref "U5") (pin "1") (pinfunction "IN_1") (pintype "bidirectional"))
      (node (ref "U5") (pin "3") (pinfunction "EN_3") (pintype "bidirectional"))
    )
    (net (code "54") (name "unconnected-(J1-ID-Pad4)") (class "Default")
      (node (ref "J1") (pin "4") (pinfunction "ID_4") (pintype "passive"))
    )
    (net (code "55") (name "unconnected-(J2-RING1_SWITCH-Pad11)") (class "Default")
      (node (ref "J2") (pin "11") (pinfunction "RING1_SWITCH_11") (pintype "passive"))
    )
    (net (code "56") (name "unconnected-(J2-TIP_SWITCH-Pad10)") (class "Default")
      (node (ref "J2") (pin "10") (pinfunction "TIP_SWITCH_10") (pintype "passive"))
    )
    (net (code "57") (name "unconnected-(U1-ZEROL-Pad23)") (class "Default")
      (node (ref "U1") (pin "23") (pinfunction "ZEROL_23") (pintype "bidirectional"))
    )
    (net (code "58") (name "unconnected-(U1-ZEROR-Pad22)") (class "Default")
      (node (ref "U1") (pin "22") (pinfunction "ZEROR_22") (pintype "bidirectional"))
    )
    (net (code "59") (name "unconnected-(U4-RB2-Pad14)") (class "Default")
      (node (ref "U4") (pin "14") (pinfunction "RB2_14") (pintype "bidirectional"))
    )
    (net (code "60") (name "unconnected-(U4-RB5-Pad11)") (class "Default")
      (node (ref "U4") (pin "11") (pinfunction "RB5_11") (pintype "bidirectional"))
    )
    (net (code "61") (name "unconnected-(U4-RB9-Pad22)") (class "Default")
      (node (ref "U4") (pin "22") (pinfunction "RB9_22") (pintype "bidirectional"))
    )
    (net (code "62") (name "unconnected-(U4-RB11-Pad24)") (class "Default")
      (node (ref "U4") (pin "24") (pinfunction "RB11_24") (pintype "bidirectional"))
    )
    (net (code "63") (name "unconnected-(U4-RB12-Pad27)") (class "Default")
      (node (ref "U4") (pin "27") (pinfunction "RB12_27") (pintype "bidirectional"))
    )
    (net (code "64") (name "unconnected-(U4-RB13-Pad28)") (class "Default")
      (node (ref "U4") (pin "28") (pinfunction "RB13_28") (pintype "bidirectional"))
    )
    (net (code "65") (name "unconnected-(U4-RB15-Pad30)") (class "Default")
      (node (ref "U4") (pin "30") (pinfunction "RB15_30") (pintype "bidirectional"))
    )
    (net (code "66") (name "unconnected-(U4-RC13-Pad47)") (class "Default")
      (node (ref "U4") (pin "47") (pinfunction "RC13_47") (pintype "bidirectional"))
    )
    (net (code "67") (name "unconnected-(U4-RC14-Pad48)") (class "Default")
      (node (ref "U4") (pin "48") (pinfunction "RC14_48") (pintype "bidirectional"))
    )
    (net (code "68") (name "unconnected-(U4-RD0-Pad46)") (class "Default")
      (node (ref "U4") (pin "46") (pinfunction "RD0_46") (pintype "bidirectional"))
    )
    (net (code "69") (name "unconnected-(U4-RD1-Pad49)") (class "Default")
      (node (ref "U4") (pin "49") (pinfunction "RD1_49") (pintype "bidirectional"))
    )
    (net (code "70") (name "unconnected-(U4-RD2-Pad50)") (class "Default")
      (node (ref "U4") (pin "50") (pinfunction "RD2_50") (pintype "bidirectional"))
    )
    (net (code "71") (name "unconnected-(U4-RD3-Pad51)") (class "Default")
      (node (ref "U4") (pin "51") (pinfunction "RD3_51") (pintype "bidirectional"))
    )
    (net (code "72") (name "unconnected-(U4-RD4-Pad52)") (class "Default")
      (node (ref "U4") (pin "52") (pinfunction "RD4_52") (pintype "bidirectional"))
    )
    (net (code "73") (name "unconnected-(U4-RD5-Pad53)") (class "Default")
      (node (ref "U4") (pin "53") (pinfunction "RD5_53") (pintype "bidirectional"))
    )
    (net (code "74") (name "unconnected-(U4-RD9-Pad43)") (class "Default")
      (node (ref "U4") (pin "43") (pinfunction "RD9_43") (pintype "bidirectional"))
    )
    (net (code "75") (name "unconnected-(U4-RD10-Pad44)") (class "Default")
      (node (ref "U4") (pin "44") (pinfunction "RD10_44") (pintype "bidirectional"))
    )
    (net (code "76") (name "unconnected-(U4-RD11-Pad45)") (class "Default")
      (node (ref "U4") (pin "45") (pinfunction "RD11_45") (pintype "bidirectional"))
    )
    (net (code "77") (name "unconnected-(U4-RE0-Pad58)") (class "Default")
      (node (ref "U4") (pin "58") (pinfunction "RE0_58") (pintype "bidirectional"))
    )
    (net (code "78") (name "unconnected-(U4-RE1-Pad61)") (class "Default")
      (node (ref "U4") (pin "61") (pinfunction "RE1_61") (pintype "bidirectional"))
    )
    (net (code "79") (name "unconnected-(U4-RE2-Pad62)") (class "Default")
      (node (ref "U4") (pin "62") (pinfunction "RE2_62") (pintype "bidirectional"))
    )
    (net (code "80") (name "unconnected-(U4-RE3-Pad63)") (class "Default")
      (node (ref "U4") (pin "63") (pinfunction "RE3_63") (pintype "bidirectional"))
    )
    (net (code "81") (name "unconnected-(U4-RE4-Pad64)") (class "Default")
      (node (ref "U4") (pin "64") (pinfunction "RE4_64") (pintype "bidirectional"))
    )
    (net (code "82") (name "unconnected-(U4-RE6-Pad2)") (class "Default")
      (node (ref "U4") (pin "2") (pinfunction "RE6_2") (pintype "bidirectional"))
    )
    (net (code "83") (name "unconnected-(U4-RE7-Pad3)") (class "Default")
      (node (ref "U4") (pin "3") (pinfunction "RE7_3") (pintype "bidirectional"))
    )
    (net (code "84") (name "unconnected-(U4-RF0-Pad56)") (class "Default")
      (node (ref "U4") (pin "56") (pinfunction "RF0_56") (pintype "bidirectional"))
    )
    (net (code "85") (name "unconnected-(U4-RF1-Pad57)") (class "Default")
      (node (ref "U4") (pin "57") (pinfunction "RF1_57") (pintype "bidirectional"))
    )
    (net (code "86") (name "unconnected-(U4-RF3-Pad38)") (class "Default")
      (node (ref "U4") (pin "38") (pinfunction "RF3_38") (pintype "bidirectional"))
    )
    (net (code "87") (name "unconnected-(U4-RF4-Pad41)") (class "Default")
      (node (ref "U4") (pin "41") (pinfunction "RF4_41") (pintype "bidirectional"))
    )
  )
)
